# Interfaces.net
KiCad netlist of a schematic drawn in Altium Designer
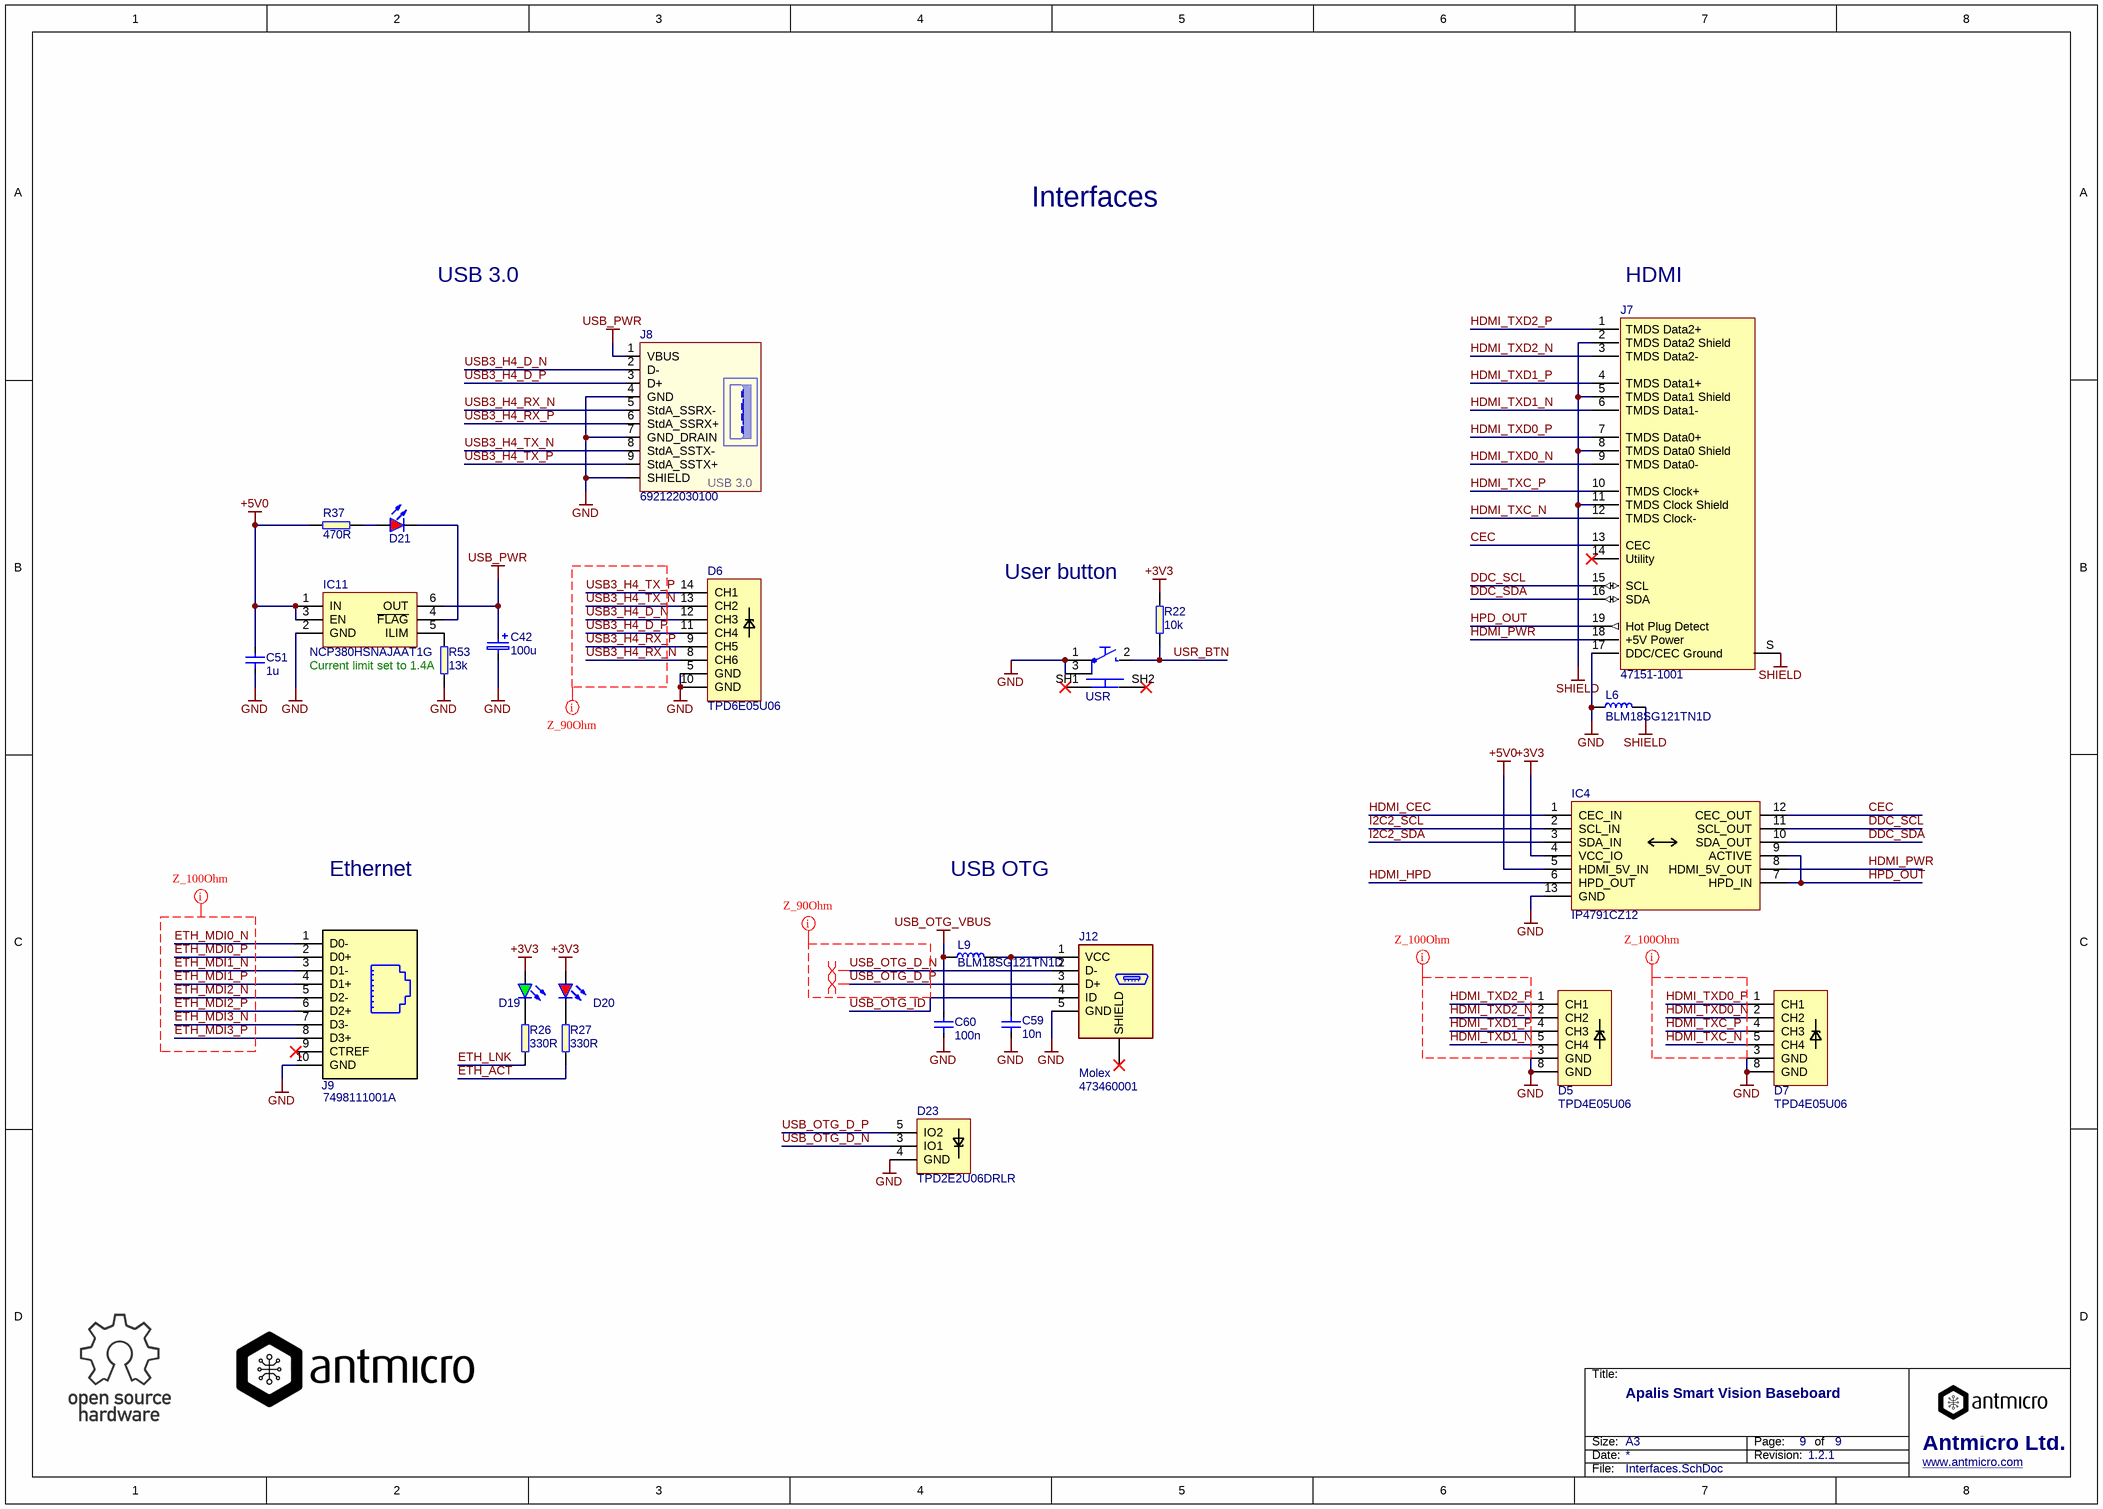
[diagram p0: Interfaces.SchDoc]

(export (version "E")
  (design (tool "Eeschema 10.0.6"))
  (components
    (comp (ref "C42")
      (value "100u")
      (footprint "KEMET_A")
      (description "Tantalum SMT Capacitor 100uF Case KEMET_A")
      (fields (field (name "PART NUMBER") "C_100u_KEMET_A") (field (name "MANUFACTURER") "VISHAY"))
      (libsource (lib "TK1Baseboard") (part "C_100u_KEMET_A"))
    )
    (comp (ref "C51")
      (value "1u")
      (footprint "0402")
      (description "MLCC SMT Capacitor 1uF 0402")
      (fields (field (name "MANUFACTURER") "MULTICOMP") (field (name "PART NUMBER") "C_1u_0402"))
      (libsource (lib "TK1Baseboard") (part "C_1u_0402"))
    )
    (comp (ref "C59")
      (value "10n")
      (footprint "0402")
      (description "MLCC SMT Capacitor 10 nF 0402")
      (fields (field (name "MANUFACTURER") "AVX") (field (name "PART NUMBER") "C_10n_0402"))
      (libsource (lib "TK1Baseboard") (part "C_10n_0402"))
    )
    (comp (ref "C60")
      (value "100n")
      (footprint "0402")
      (description "MLCC SMT Capacitor 100n 0402")
      (fields (field (name "MANUFACTURER") "TDK") (field (name "PART NUMBER") "C_100n_0402"))
      (libsource (lib "TK1Baseboard") (part "C_100n_0402"))
    )
    (comp (ref "D5")
      (value "TPD4E05U06")
      (footprint "TPD4E05U06_PASS")
      (description "ESD Suppressors 4-CH")
      (fields
        (field (name "PART NUMBER") "TPD4E05U06_PASS")
        (field (name "MANUFACTURER") "Texas Instruments")
      )
      (libsource (lib "TK1Baseboard") (part "TPD4E05U06_PASS"))
    )
    (comp (ref "D6")
      (value "TPD6E05U06")
      (footprint "TPD6E05U06_PASS")
      (description "ESD Suppressors 6-CH Pass through layout")
      (fields
        (field (name "PART NUMBER") "TPD6E05U06_PASS")
        (field (name "MANUFACTURER") "Texas Instruments")
      )
      (libsource (lib "TK1Baseboard") (part "TPD6E05U06_PASS"))
    )
    (comp (ref "D7")
      (value "TPD4E05U06")
      (footprint "TPD4E05U06_PASS")
      (description "ESD Suppressors 4-CH")
      (fields
        (field (name "PART NUMBER") "TPD4E05U06_PASS")
        (field (name "MANUFACTURER") "Texas Instruments")
      )
      (libsource (lib "TK1Baseboard") (part "TPD4E05U06_PASS"))
    )
    (comp (ref "D19")
      (value "KPJA-2107CKCK")
      (footprint "KPJA-2107")
      (description "LED Green 0603 case")
      (fields (field (name "PART NUMBER") "LED_G") (field (name "MANUFACTURER") "KINGBRIGHT"))
      (libsource (lib "TK1Baseboard") (part "KPJA-2107CKCK"))
    )
    (comp (ref "D20")
      (value "KPJA-2107SYCK")
      (footprint "KPJA-2107")
      (description "LED Red 0603 case")
      (fields (field (name "PART NUMBER") "LED_R") (field (name "MANUFACTURER") "KINGBRIGHT"))
      (libsource (lib "TK1Baseboard") (part "KPJA-2107SYCK"))
    )
    (comp (ref "D21")
      (value "KPT-1608EC")
      (footprint "LED0603")
      (description "LED Red 0603 case")
      (fields (field (name "PART NUMBER") "LED_R") (field (name "MANUFACTURER") "KINGBRIGHT"))
      (libsource (lib "TK1Baseboard") (part "LED_R"))
    )
    (comp (ref "D23")
      (value "TPD2E2U06DRLR")
      (footprint "TPD2E2U06DRLR")
      (description "ESD Suppressors 2-CH")
      (fields (field (name "PART NUMBER") "TPD2E2U06") (field (name "MANUFACTURER") "Texas Instruments"))
      (libsource (lib "TK1Baseboard") (part "TPD2E2U06"))
    )
    (comp (ref "IC4")
      (value "IP4791CZ12")
      (footprint "IP4791CZ12")
      (description "HDMI DEVICE, ESD PROTECTION")
      (fields (field (name "MANUFACTURER") "NXP"))
      (libsource (lib "TK1Baseboard") (part "IP4791CZ12"))
    )
    (comp (ref "IC11")
      (value "NCP380HSNAJAAT1G")
      (footprint "TSOP-6")
      (description "POWER LOAD SWITCH, HIGH SIDE")
      (fields (field (name "MANUFACTURER") "ON Semiconductor"))
      (libsource (lib "TK1Baseboard") (part "NCP380HSNAJAAT1G"))
    )
    (comp (ref "J7")
      (value "47151-1001")
      (footprint "Molex_HDMI_471511001")
      (description "Header right angle HDMI")
      (fields (field (name "PART NUMBER") "CON-Molex-471511001") (field (name "MANUFACTURER") "MOLEX"))
      (libsource (lib "TK1Baseboard") (part "CON-Molex-471511001"))
    )
    (comp (ref "J8")
      (value "692122030100")
      (footprint "692122030100")
      (description "USB 3.0 Type A Horizontal SMD WR-COM")
      (fields
        (field (name "MANUFACTURER") "WURTH ELEKTRONIK")
        (field (name "PART NUMBER") "WE-692-122-030-100")
      )
      (libsource (lib "TK1Baseboard") (part "USB_3_A"))
    )
    (comp (ref "J9")
      (value "7498111001A")
      (footprint "7498111001A")
      (description "RJ-45 with Transofrmer, 10/100/1000 Base-T")
      (fields
        (field (name "MANUFACTURER") "WURTH ELEKTRONIK")
        (field (name "PART NUMBER") "WE-749-811-100-1A")
      )
      (libsource (lib "TK1Baseboard") (part "RJ-45-10"))
    )
    (comp (ref "J12")
      (value "Molex 47346-0001")
      (footprint "CON-Molex-047346-0001")
      (description "USB - micro B Receptacle Connector 5 Position Surface Mount, Right Angle, Horizontal")
      (fields
        (field (name "PART NUMBER") "CON-Molex-47346-0001")
        (field (name "MANUFACTURER") "Molex")
        (field (name "PART SYMBOL") "473460001")
        (field (name "MPN") "473460001")
      )
      (libsource (lib "TK1Baseboard") (part "Micro USB B"))
    )
    (comp (ref "L6")
      (value "BLM18SG121TN1D")
      (footprint "0603")
      (description "FERRITE BEAD, 0.025OHM, 3A, 0603")
      (fields (field (name "MANUFACTURER") "MURATA"))
      (libsource (lib "TK1Baseboard") (part "BLM18SG121TN1D"))
    )
    (comp (ref "L9")
      (value "BLM18SG121TN1D")
      (footprint "0603")
      (description "FERRITE BEAD, 0.025OHM, 3A, 0603")
      (fields (field (name "MANUFACTURER") "MURATA"))
      (libsource (lib "TK1Baseboard") (part "BLM18SG121TN1D"))
    )
    (comp (ref "R22")
      (value "10k")
      (footprint "0402")
      (description "RES, 10k, 0402")
      (fields (field (name "MANUFACTURER") "MULTICOMP") (field (name "PART NUMBER") "R_10k_0402"))
      (libsource (lib "TK1Baseboard") (part "R_10k_0402"))
    )
    (comp (ref "R26")
      (value "330R")
      (footprint "0402")
      (description "RES, 330R, 0402")
      (fields (field (name "MANUFACTURER") "MULTICOMP") (field (name "PART NUMBER") "R_330R_0402"))
      (libsource (lib "TK1Baseboard") (part "R_330R_0402"))
    )
    (comp (ref "R27")
      (value "330R")
      (footprint "0402")
      (description "RES, 330R, 0402")
      (fields (field (name "MANUFACTURER") "MULTICOMP") (field (name "PART NUMBER") "R_330R_0402"))
      (libsource (lib "TK1Baseboard") (part "R_330R_0402"))
    )
    (comp (ref "R37")
      (value "470R")
      (footprint "0402")
      (description "RES, 470R, 0402")
      (fields (field (name "MANUFACTURER") "VISHAY") (field (name "PART NUMBER") "R_470R_0402"))
      (libsource (lib "TK1Baseboard") (part "R_470R_0402"))
    )
    (comp (ref "R53")
      (value "13k")
      (footprint "0402")
      (description "RES, 13k, 0402")
      (fields (field (name "MANUFACTURER") "Panasonic") (field (name "PART NUMBER") "R_13k_0402"))
      (libsource (lib "TK1Baseboard") (part "R_13k_0402"))
    )
    (comp (ref "USR")
      (value "TL3340AF160QG")
      (footprint "TL3340AF160QG")
      (description "E-SWITCH  TL3340AF160QG  SWITCH, TACTILE SPST 50mA, SMD GULL WING")
      (fields (field (name "MANUFACTURER") "E-SWITCH"))
      (libsource (lib "TK1Baseboard") (part "TL3340AF160QG"))
    )
  )
  (nets
    (net (code "1") (name "+3V3") (class "Default")
      (node (ref "D19") (pin "A") (pinfunction "A_A") (pintype "passive"))
      (node (ref "D20") (pin "A") (pinfunction "A_A") (pintype "passive"))
      (node (ref "IC4") (pin "4") (pinfunction "VCC_IO_4") (pintype "passive"))
      (node (ref "R22") (pin "2") (pintype "passive"))
    )
    (net (code "2") (name "+5V0") (class "Default")
      (node (ref "C51") (pin "2") (pinfunction "2_2") (pintype "passive"))
      (node (ref "IC11") (pin "1") (pinfunction "IN_1") (pintype "passive"))
      (node (ref "IC11") (pin "3") (pinfunction "EN_3") (pintype "passive"))
      (node (ref "IC4") (pin "5") (pinfunction "HDMI_5V_IN_5") (pintype "passive"))
      (node (ref "R37") (pin "2") (pintype "passive"))
    )
    (net (code "3") (name "/CEC") (class "Default")
      (node (ref "IC4") (pin "12") (pinfunction "CEC_OUT_12") (pintype "passive"))
      (node (ref "J7") (pin "13") (pinfunction "CEC_13") (pintype "passive"))
    )
    (net (code "4") (name "/DDC_SCL") (class "Default")
      (node (ref "IC4") (pin "11") (pinfunction "SCL_OUT_11") (pintype "passive"))
      (node (ref "J7") (pin "15") (pinfunction "SCL_15") (pintype "bidirectional"))
    )
    (net (code "5") (name "/DDC_SDA") (class "Default")
      (node (ref "IC4") (pin "10") (pinfunction "SDA_OUT_10") (pintype "passive"))
      (node (ref "J7") (pin "16") (pinfunction "SDA_16") (pintype "bidirectional"))
    )
    (net (code "6") (name "/ETH_ACT") (class "Default") (node (ref "R27") (pin "2") (pintype "passive")))
    (net (code "7") (name "/ETH_LNK") (class "Default") (node (ref "R26") (pin "2") (pintype "passive")))
    (net (code "8") (name "/ETH_MDI0_N") (class "Default")
      (node (ref "J9") (pin "1") (pinfunction "D0-_1") (pintype "passive"))
    )
    (net (code "9") (name "/ETH_MDI0_P") (class "Default")
      (node (ref "J9") (pin "2") (pinfunction "D0+_2") (pintype "passive"))
    )
    (net (code "10") (name "/ETH_MDI1_N") (class "Default")
      (node (ref "J9") (pin "3") (pinfunction "D1-_3") (pintype "passive"))
    )
    (net (code "11") (name "/ETH_MDI1_P") (class "Default")
      (node (ref "J9") (pin "4") (pinfunction "D1+_4") (pintype "passive"))
    )
    (net (code "12") (name "/ETH_MDI2_N") (class "Default")
      (node (ref "J9") (pin "5") (pinfunction "D2-_5") (pintype "passive"))
    )
    (net (code "13") (name "/ETH_MDI2_P") (class "Default")
      (node (ref "J9") (pin "6") (pinfunction "D2+_6") (pintype "passive"))
    )
    (net (code "14") (name "/ETH_MDI3_N") (class "Default")
      (node (ref "J9") (pin "7") (pinfunction "D3-_7") (pintype "passive"))
    )
    (net (code "15") (name "/ETH_MDI3_P") (class "Default")
      (node (ref "J9") (pin "8") (pinfunction "D3+_8") (pintype "passive"))
    )
    (net (code "16") (name "/HDMI_CEC") (class "Default")
      (node (ref "IC4") (pin "1") (pinfunction "CEC_IN_1") (pintype "passive"))
    )
    (net (code "17") (name "/HDMI_HPD") (class "Default")
      (node (ref "IC4") (pin "6") (pinfunction "HPD_OUT_6") (pintype "passive"))
    )
    (net (code "18") (name "/HDMI_PWR") (class "Default")
      (node (ref "IC4") (pin "8") (pinfunction "HDMI_5V_OUT_8") (pintype "passive"))
      (node (ref "J7") (pin "18") (pinfunction "+5V_Power_18") (pintype "power_in"))
    )
    (net (code "19") (name "/HDMI_TXC_N") (class "Default")
      (node (ref "D7") (pin "5") (pinfunction "CH4_5") (pintype "passive"))
      (node (ref "J7") (pin "12") (pinfunction "TMDS_Clock-_12") (pintype "passive"))
    )
    (net (code "20") (name "/HDMI_TXC_P") (class "Default")
      (node (ref "D7") (pin "4") (pinfunction "CH3_4") (pintype "passive"))
      (node (ref "J7") (pin "10") (pinfunction "TMDS_Clock+_10") (pintype "passive"))
    )
    (net (code "21") (name "/HDMI_TXD0_N") (class "Default")
      (node (ref "D7") (pin "2") (pinfunction "CH2_2") (pintype "passive"))
      (node (ref "J7") (pin "9") (pinfunction "TMDS_Data0-_9") (pintype "passive"))
    )
    (net (code "22") (name "/HDMI_TXD0_P") (class "Default")
      (node (ref "D7") (pin "1") (pinfunction "CH1_1") (pintype "passive"))
      (node (ref "J7") (pin "7") (pinfunction "TMDS_Data0+_7") (pintype "passive"))
    )
    (net (code "23") (name "/HDMI_TXD1_N") (class "Default")
      (node (ref "D5") (pin "5") (pinfunction "CH4_5") (pintype "passive"))
      (node (ref "J7") (pin "6") (pinfunction "TMDS_Data1-_6") (pintype "passive"))
    )
    (net (code "24") (name "/HDMI_TXD1_P") (class "Default")
      (node (ref "D5") (pin "4") (pinfunction "CH3_4") (pintype "passive"))
      (node (ref "J7") (pin "4") (pinfunction "TMDS_Data1+_4") (pintype "passive"))
    )
    (net (code "25") (name "/HDMI_TXD2_N") (class "Default")
      (node (ref "D5") (pin "2") (pinfunction "CH2_2") (pintype "passive"))
      (node (ref "J7") (pin "3") (pinfunction "TMDS_Data2-_3") (pintype "passive"))
    )
    (net (code "26") (name "/HDMI_TXD2_P") (class "Default")
      (node (ref "D5") (pin "1") (pinfunction "CH1_1") (pintype "passive"))
      (node (ref "J7") (pin "1") (pinfunction "TMDS_Data2+_1") (pintype "passive"))
    )
    (net (code "27") (name "/HPD_OUT") (class "Default")
      (node (ref "IC4") (pin "7") (pinfunction "HPD_IN_7") (pintype "passive"))
      (node (ref "IC4") (pin "9") (pinfunction "ACTIVE_9") (pintype "passive"))
      (node (ref "J7") (pin "19") (pinfunction "Hot_Plug_Detect_19") (pintype "output"))
    )
    (net (code "28") (name "/I2C2_SCL") (class "Default")
      (node (ref "IC4") (pin "2") (pinfunction "SCL_IN_2") (pintype "passive"))
    )
    (net (code "29") (name "/I2C2_SDA") (class "Default")
      (node (ref "IC4") (pin "3") (pinfunction "SDA_IN_3") (pintype "passive"))
    )
    (net (code "30") (name "/USB3_H4_D_N") (class "Default")
      (node (ref "D6") (pin "12") (pinfunction "CH3_12") (pintype "passive"))
      (node (ref "J8") (pin "2") (pinfunction "D-_2") (pintype "passive"))
    )
    (net (code "31") (name "/USB3_H4_D_P") (class "Default")
      (node (ref "D6") (pin "11") (pinfunction "CH4_11") (pintype "passive"))
      (node (ref "J8") (pin "3") (pinfunction "D+_3") (pintype "passive"))
    )
    (net (code "32") (name "/USB3_H4_RX_N") (class "Default")
      (node (ref "D6") (pin "8") (pinfunction "CH6_8") (pintype "passive"))
      (node (ref "J8") (pin "5") (pinfunction "StdA_SSRX-_5") (pintype "passive"))
    )
    (net (code "33") (name "/USB3_H4_RX_P") (class "Default")
      (node (ref "D6") (pin "9") (pinfunction "CH5_9") (pintype "passive"))
      (node (ref "J8") (pin "6") (pinfunction "StdA_SSRX+_6") (pintype "passive"))
    )
    (net (code "34") (name "/USB3_H4_TX_N") (class "Default")
      (node (ref "D6") (pin "13") (pinfunction "CH2_13") (pintype "passive"))
      (node (ref "J8") (pin "8") (pinfunction "StdA_SSTX-_8") (pintype "passive"))
    )
    (net (code "35") (name "/USB3_H4_TX_P") (class "Default")
      (node (ref "D6") (pin "14") (pinfunction "CH1_14") (pintype "passive"))
      (node (ref "J8") (pin "9") (pinfunction "StdA_SSTX+_9") (pintype "passive"))
    )
    (net (code "36") (name "/USB_OTG_D_N") (class "Default")
      (node (ref "D23") (pin "3") (pinfunction "IO1_3") (pintype "passive"))
      (node (ref "J12") (pin "2") (pinfunction "D-_2") (pintype "passive"))
    )
    (net (code "37") (name "/USB_OTG_D_P") (class "Default")
      (node (ref "D23") (pin "5") (pinfunction "IO2_5") (pintype "passive"))
      (node (ref "J12") (pin "3") (pinfunction "D+_3") (pintype "passive"))
    )
    (net (code "38") (name "/USB_OTG_ID") (class "Default")
      (node (ref "J12") (pin "4") (pinfunction "ID_4") (pintype "passive"))
    )
    (net (code "39") (name "/USR_BTN") (class "Default")
      (node (ref "R22") (pin "1") (pintype "passive"))
      (node (ref "USR") (pin "2") (pinfunction "2_2") (pintype "passive"))
    )
    (net (code "40") (name "GND") (class "Default")
      (node (ref "C42") (pin "2") (pinfunction "2_2") (pintype "passive"))
      (node (ref "C51") (pin "1") (pinfunction "1_1") (pintype "passive"))
      (node (ref "C59") (pin "2") (pinfunction "2_2") (pintype "passive"))
      (node (ref "C60") (pin "1") (pinfunction "1_1") (pintype "passive"))
      (node (ref "D23") (pin "4") (pinfunction "GND_4") (pintype "passive"))
      (node (ref "D5") (pin "3") (pinfunction "GND_3") (pintype "passive"))
      (node (ref "D5") (pin "8") (pinfunction "GND_8") (pintype "passive"))
      (node (ref "D6") (pin "10") (pinfunction "GND_10") (pintype "passive"))
      (node (ref "D6") (pin "5") (pinfunction "GND_5") (pintype "passive"))
      (node (ref "D7") (pin "3") (pinfunction "GND_3") (pintype "passive"))
      (node (ref "D7") (pin "8") (pinfunction "GND_8") (pintype "passive"))
      (node (ref "IC11") (pin "2") (pinfunction "GND_2") (pintype "passive"))
      (node (ref "IC4") (pin "13") (pinfunction "GND_13") (pintype "passive"))
      (node (ref "J12") (pin "5") (pinfunction "GND_5") (pintype "power_in"))
      (node (ref "J7") (pin "17") (pinfunction "DDC/CEC_Ground_17") (pintype "power_in"))
      (node (ref "J8") (pin "4") (pinfunction "GND_4") (pintype "passive"))
      (node (ref "J8") (pin "7") (pinfunction "GND_DRAIN_7") (pintype "passive"))
      (node (ref "J8") (pin "SHIELD") (pinfunction "SHIELD_SHIELD") (pintype "passive"))
      (node (ref "J9") (pin "10") (pinfunction "GND_10") (pintype "passive"))
      (node (ref "L6") (pin "1") (pintype "passive"))
      (node (ref "R53") (pin "1") (pintype "passive"))
      (node (ref "USR") (pin "1") (pinfunction "1_1") (pintype "passive"))
      (node (ref "USR") (pin "3") (pinfunction "3_3") (pintype "passive"))
    )
    (net (code "41") (name "Net-(D19-PadK)") (class "Default")
      (node (ref "D19") (pin "K") (pinfunction "K_K") (pintype "passive"))
      (node (ref "R26") (pin "1") (pintype "passive"))
    )
    (net (code "42") (name "Net-(D20-PadK)") (class "Default")
      (node (ref "D20") (pin "K") (pinfunction "K_K") (pintype "passive"))
      (node (ref "R27") (pin "1") (pintype "passive"))
    )
    (net (code "43") (name "Net-(D21-PadA)") (class "Default")
      (node (ref "D21") (pin "A") (pinfunction "A_A") (pintype "passive"))
      (node (ref "R37") (pin "1") (pintype "passive"))
    )
    (net (code "44") (name "Net-(IC11-ILIM)") (class "Default")
      (node (ref "IC11") (pin "5") (pinfunction "ILIM_5") (pintype "passive"))
      (node (ref "R53") (pin "2") (pintype "passive"))
    )
    (net (code "45") (name "Net-(IC11-~{FLAG})") (class "Default")
      (node (ref "D21") (pin "K") (pinfunction "K_K") (pintype "passive"))
      (node (ref "IC11") (pin "4") (pinfunction "~{FLAG}_4") (pintype "passive"))
    )
    (net (code "46") (name "Net-(J12-VCC)") (class "Default")
      (node (ref "C59") (pin "1") (pinfunction "1_1") (pintype "passive"))
      (node (ref "J12") (pin "1") (pinfunction "VCC_1") (pintype "power_in"))
      (node (ref "L9") (pin "2") (pintype "passive"))
    )
    (net (code "47") (name "SHIELD") (class "Default")
      (node (ref "J7") (pin "11") (pinfunction "TMDS_Clock_Shield_11") (pintype "passive"))
      (node (ref "J7") (pin "2") (pinfunction "TMDS_Data2_Shield_2") (pintype "passive"))
      (node (ref "J7") (pin "5") (pinfunction "TMDS_Data1_Shield_5") (pintype "passive"))
      (node (ref "J7") (pin "8") (pinfunction "TMDS_Data0_Shield_8") (pintype "passive"))
      (node (ref "J7") (pin "S") (pinfunction "SH_S") (pintype "passive"))
      (node (ref "L6") (pin "2") (pintype "passive"))
    )
    (net (code "48") (name "USB_OTG_VBUS") (class "Default")
      (node (ref "C60") (pin "2") (pinfunction "2_2") (pintype "passive"))
      (node (ref "L9") (pin "1") (pintype "passive"))
    )
    (net (code "49") (name "USB_PWR") (class "Default")
      (node (ref "C42") (pin "1") (pinfunction "1_1") (pintype "passive"))
      (node (ref "IC11") (pin "6") (pinfunction "OUT_6") (pintype "passive"))
      (node (ref "J8") (pin "1") (pinfunction "VBUS_1") (pintype "passive"))
    )
    (net (code "50") (name "unconnected-(J7-Utility-Pad14)") (class "Default")
      (node (ref "J7") (pin "14") (pinfunction "Utility_14") (pintype "passive+no_connect"))
    )
    (net (code "51") (name "unconnected-(J9-CTREF-Pad9)") (class "Default")
      (node (ref "J9") (pin "9") (pinfunction "CTREF_9") (pintype "passive+no_connect"))
    )
    (net (code "52") (name "unconnected-(J12-SHIELD-PadS)") (class "Default")
      (node (ref "J12") (pin "S") (pinfunction "SHIELD_S") (pintype "passive+no_connect"))
    )
    (net (code "53") (name "unconnected-(USR-PadSH1)") (class "Default")
      (node (ref "USR") (pin "SH1") (pinfunction "SH1_SH1") (pintype "passive+no_connect"))
    )
    (net (code "54") (name "unconnected-(USR-PadSH2)") (class "Default")
      (node (ref "USR") (pin "SH2") (pinfunction "SH2_SH2") (pintype "passive+no_connect"))
    )
  )
)
